# esp8266-proto-board-1206.net
KiCad netlist of a schematic drawn in EAGLE
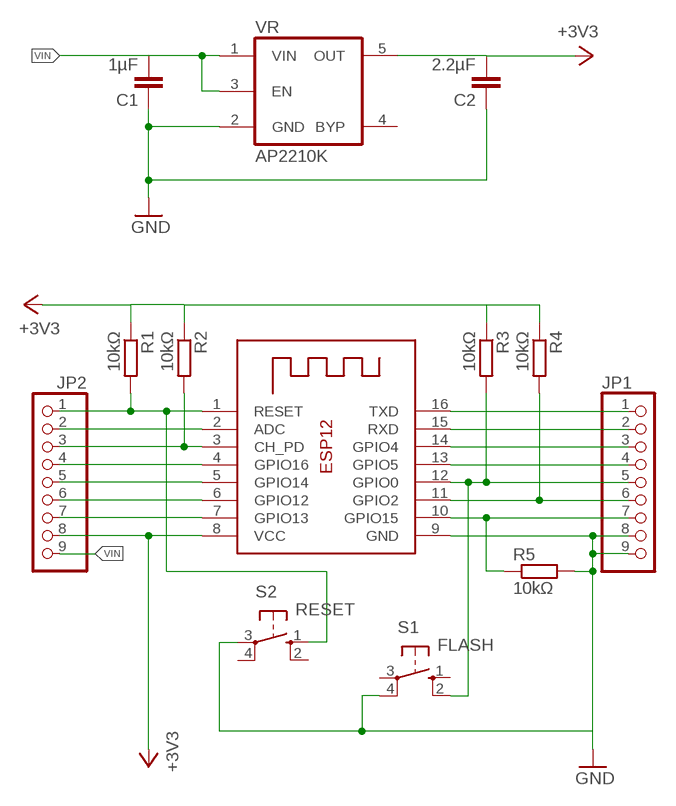
[diagram p0: schematic, sheet 1]

(export (version "E")
  (design (tool "Eeschema 10.0.6"))
  (components
    (comp (ref "C1")
      (value "1µF")
      (footprint "eagle-import:C1206")
      (libsource (lib "eagle-import") (part "C-EUC1206"))
    )
    (comp (ref "C2")
      (value "2.2µF")
      (footprint "eagle-import:C1206")
      (libsource (lib "eagle-import") (part "C-EUC1206"))
    )
    (comp (ref "JP1")
      (value "PINHD-1X9")
      (footprint "eagle-import:1X09-BIG")
      (libsource (lib "eagle-import") (part "PINHD-1X9"))
    )
    (comp (ref "JP2")
      (value "PINHD-1X9")
      (footprint "eagle-import:1X09-BIG")
      (libsource (lib "eagle-import") (part "PINHD-1X9"))
    )
    (comp (ref "R1")
      (value "10kΩ")
      (footprint "eagle-import:M1206")
      (libsource (lib "eagle-import") (part "R-EU_M1206"))
    )
    (comp (ref "R2")
      (value "10kΩ")
      (footprint "eagle-import:M1206")
      (libsource (lib "eagle-import") (part "R-EU_M1206"))
    )
    (comp (ref "R3")
      (value "10kΩ")
      (footprint "eagle-import:M1206")
      (libsource (lib "eagle-import") (part "R-EU_M1206"))
    )
    (comp (ref "R4")
      (value "10kΩ")
      (footprint "eagle-import:M1206")
      (libsource (lib "eagle-import") (part "R-EU_M1206"))
    )
    (comp (ref "R5")
      (value "10kΩ")
      (footprint "eagle-import:M1206")
      (libsource (lib "eagle-import") (part "R-EU_M1206"))
    )
    (comp (ref "S1")
      (value "FLASH")
      (footprint "eagle-import:B3F-10XX")
      (fields (field (name "MPN") "B3F-1000"))
      (libsource (lib "eagle-import") (part "10-XX"))
    )
    (comp (ref "S2")
      (value "RESET")
      (footprint "eagle-import:B3F-10XX")
      (fields (field (name "MPN") "B3F-1000"))
      (libsource (lib "eagle-import") (part "10-XX"))
    )
    (comp (ref "U1")
      (value "ESP-12")
      (footprint "eagle-import:ESP-12")
      (libsource (lib "eagle-import") (part "ESP-12"))
    )
    (comp (ref "VR")
      (value "AP2210K")
      (footprint "eagle-import:SOT23-5")
      (libsource (lib "eagle-import") (part "AP2210K"))
    )
  )
  (nets
    (net (code "1") (name "+3V3") (class "Default")
      (node (ref "C2") (pin "2") (pinfunction "2_2") (pintype "passive"))
      (node (ref "JP2") (pin "8") (pinfunction "8_8") (pintype "passive"))
      (node (ref "R1") (pin "1") (pinfunction "1_1") (pintype "passive"))
      (node (ref "R2") (pin "1") (pinfunction "1_1") (pintype "passive"))
      (node (ref "R3") (pin "1") (pinfunction "1_1") (pintype "passive"))
      (node (ref "R4") (pin "1") (pinfunction "1_1") (pintype "passive"))
      (node (ref "U1") (pin "8") (pinfunction "VCC_8") (pintype "power_in"))
      (node (ref "VR") (pin "5") (pinfunction "OUT_5") (pintype "power_in"))
    )
    (net (code "2") (name "GND") (class "Default")
      (node (ref "C1") (pin "1") (pinfunction "1_1") (pintype "passive"))
      (node (ref "C2") (pin "1") (pinfunction "1_1") (pintype "passive"))
      (node (ref "JP1") (pin "8") (pinfunction "8_8") (pintype "passive"))
      (node (ref "JP1") (pin "9") (pinfunction "9_9") (pintype "passive"))
      (node (ref "R5") (pin "2") (pinfunction "2_2") (pintype "passive"))
      (node (ref "S1") (pin "4") (pinfunction "P1_4") (pintype "passive"))
      (node (ref "S2") (pin "3") (pinfunction "P_3") (pintype "passive"))
      (node (ref "U1") (pin "9") (pinfunction "GND_9") (pintype "power_in"))
      (node (ref "VR") (pin "2") (pinfunction "GND_2") (pintype "power_in"))
    )
    (net (code "3") (name "Net-(S1-S1)") (class "Default")
      (node (ref "JP1") (pin "5") (pinfunction "5_5") (pintype "passive"))
      (node (ref "R3") (pin "2") (pinfunction "2_2") (pintype "passive"))
      (node (ref "S1") (pin "2") (pinfunction "S1_2") (pintype "passive"))
      (node (ref "U1") (pin "12") (pinfunction "GPIO0_12") (pintype "bidirectional"))
    )
    (net (code "4") (name "Net-(S2-S)") (class "Default")
      (node (ref "JP2") (pin "1") (pinfunction "1_1") (pintype "passive"))
      (node (ref "R1") (pin "2") (pinfunction "2_2") (pintype "passive"))
      (node (ref "S2") (pin "1") (pinfunction "S_1") (pintype "passive"))
      (node (ref "U1") (pin "1") (pinfunction "RESET_1") (pintype "input"))
    )
    (net (code "5") (name "Net-(U1-ADC)") (class "Default")
      (node (ref "JP2") (pin "2") (pinfunction "2_2") (pintype "passive"))
      (node (ref "U1") (pin "2") (pinfunction "ADC_2") (pintype "passive"))
    )
    (net (code "6") (name "Net-(U1-CH_PD)") (class "Default")
      (node (ref "JP2") (pin "3") (pinfunction "3_3") (pintype "passive"))
      (node (ref "R2") (pin "2") (pinfunction "2_2") (pintype "passive"))
      (node (ref "U1") (pin "3") (pinfunction "CH_PD_3") (pintype "input"))
    )
    (net (code "7") (name "Net-(U1-GPIO2)") (class "Default")
      (node (ref "JP1") (pin "6") (pinfunction "6_6") (pintype "passive"))
      (node (ref "R4") (pin "2") (pinfunction "2_2") (pintype "passive"))
      (node (ref "U1") (pin "11") (pinfunction "GPIO2_11") (pintype "bidirectional"))
    )
    (net (code "8") (name "Net-(U1-GPIO4)") (class "Default")
      (node (ref "JP1") (pin "3") (pinfunction "3_3") (pintype "passive"))
      (node (ref "U1") (pin "14") (pinfunction "GPIO4_14") (pintype "bidirectional"))
    )
    (net (code "9") (name "Net-(U1-GPIO5)") (class "Default")
      (node (ref "JP1") (pin "4") (pinfunction "4_4") (pintype "passive"))
      (node (ref "U1") (pin "13") (pinfunction "GPIO5_13") (pintype "bidirectional"))
    )
    (net (code "10") (name "Net-(U1-GPIO12)") (class "Default")
      (node (ref "JP2") (pin "6") (pinfunction "6_6") (pintype "passive"))
      (node (ref "U1") (pin "6") (pinfunction "GPIO12_6") (pintype "bidirectional"))
    )
    (net (code "11") (name "Net-(U1-GPIO13)") (class "Default")
      (node (ref "JP2") (pin "7") (pinfunction "7_7") (pintype "passive"))
      (node (ref "U1") (pin "7") (pinfunction "GPIO13_7") (pintype "bidirectional"))
    )
    (net (code "12") (name "Net-(U1-GPIO14)") (class "Default")
      (node (ref "JP2") (pin "5") (pinfunction "5_5") (pintype "passive"))
      (node (ref "U1") (pin "5") (pinfunction "GPIO14_5") (pintype "bidirectional"))
    )
    (net (code "13") (name "Net-(U1-GPIO15)") (class "Default")
      (node (ref "JP1") (pin "7") (pinfunction "7_7") (pintype "passive"))
      (node (ref "R5") (pin "1") (pinfunction "1_1") (pintype "passive"))
      (node (ref "U1") (pin "10") (pinfunction "GPIO15_10") (pintype "bidirectional"))
    )
    (net (code "14") (name "Net-(U1-GPIO16)") (class "Default")
      (node (ref "JP2") (pin "4") (pinfunction "4_4") (pintype "passive"))
      (node (ref "U1") (pin "4") (pinfunction "GPIO16_4") (pintype "bidirectional"))
    )
    (net (code "15") (name "Net-(U1-RXD)") (class "Default")
      (node (ref "JP1") (pin "2") (pinfunction "2_2") (pintype "passive"))
      (node (ref "U1") (pin "15") (pinfunction "RXD_15") (pintype "input"))
    )
    (net (code "16") (name "Net-(U1-TXD)") (class "Default")
      (node (ref "JP1") (pin "1") (pinfunction "1_1") (pintype "passive"))
      (node (ref "U1") (pin "16") (pinfunction "TXD_16") (pintype "output"))
    )
    (net (code "17") (name "VIN") (class "Default")
      (node (ref "C1") (pin "2") (pinfunction "2_2") (pintype "passive"))
      (node (ref "JP2") (pin "9") (pinfunction "9_9") (pintype "passive"))
      (node (ref "VR") (pin "1") (pinfunction "VIN_1") (pintype "input"))
      (node (ref "VR") (pin "3") (pinfunction "EN_3") (pintype "input"))
    )
    (net (code "18") (name "unconnected-(S1-P-Pad3)") (class "Default")
      (node (ref "S1") (pin "3") (pinfunction "P_3") (pintype "passive"))
    )
    (net (code "19") (name "unconnected-(S1-S-Pad1)") (class "Default")
      (node (ref "S1") (pin "1") (pinfunction "S_1") (pintype "passive"))
    )
    (net (code "20") (name "unconnected-(S2-P1-Pad4)") (class "Default")
      (node (ref "S2") (pin "4") (pinfunction "P1_4") (pintype "passive"))
    )
    (net (code "21") (name "unconnected-(S2-S1-Pad2)") (class "Default")
      (node (ref "S2") (pin "2") (pinfunction "S1_2") (pintype "passive"))
    )
    (net (code "22") (name "unconnected-(VR-BYP-Pad4)") (class "Default")
      (node (ref "VR") (pin "4") (pinfunction "BYP_4") (pintype "output"))
    )
  )
)
